# mass_slit7.net
KiCad netlist of a schematic drawn in EAGLE
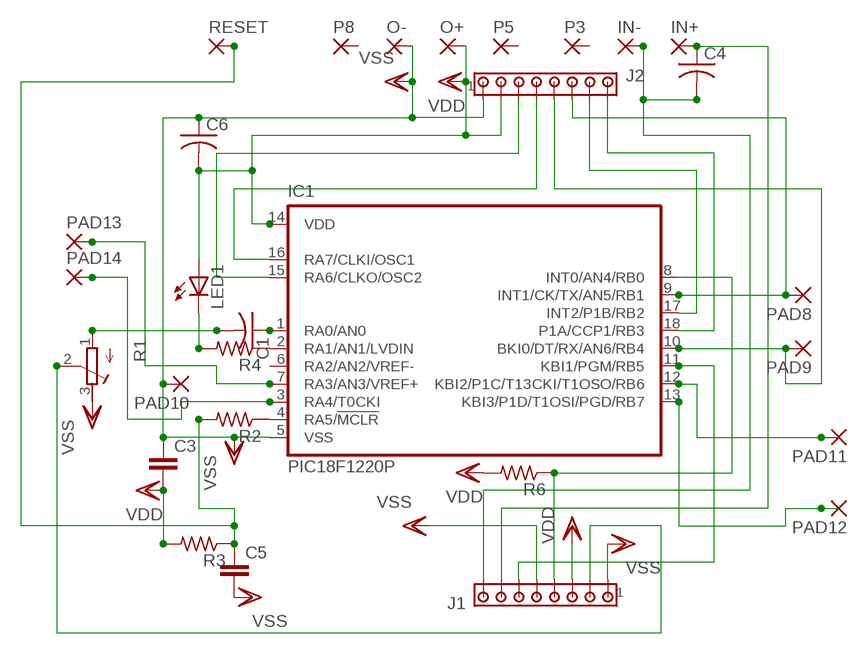
[diagram p0: schematic, sheet 1]

(export (version "E")
  (design (tool "Eeschema 10.0.6"))
  (components
    (comp (ref "C1")
      (value "C-US025-040X050")
      (footprint "eagle-import:C025-040X050")
      (libsource (lib "eagle-import") (part "C-US025-040X050"))
    )
    (comp (ref "C3")
      (value "C5/2.5")
      (footprint "eagle-import:C5B2.5")
      (libsource (lib "eagle-import") (part "C5/2.5"))
    )
    (comp (ref "C4")
      (value "C-US025-040X050")
      (footprint "eagle-import:C025-040X050")
      (libsource (lib "eagle-import") (part "C-US025-040X050"))
    )
    (comp (ref "C5")
      (value "C5/2.5")
      (footprint "eagle-import:C5B2.5")
      (libsource (lib "eagle-import") (part "C5/2.5"))
    )
    (comp (ref "C6")
      (value "C-US025-040X050")
      (footprint "eagle-import:C025-040X050")
      (libsource (lib "eagle-import") (part "C-US025-040X050"))
    )
    (comp (ref "IC1")
      (value "PIC18F1220P")
      (footprint "eagle-import:DIL18")
      (fields (field (name "MF") "MICROCHIP") (field (name "MPN") "PIC18F1220-I/P"))
      (libsource (lib "eagle-import") (part "PIC18F120P2"))
    )
    (comp (ref "IN+")
      (value "1,6/0,9")
      (footprint "eagle-import:1,6_0,9")
      (libsource (lib "eagle-import") (part "1,6/0,9"))
    )
    (comp (ref "IN-")
      (value "1,6/0,9")
      (footprint "eagle-import:1,6_0,9")
      (libsource (lib "eagle-import") (part "1,6/0,9"))
    )
    (comp (ref "J1")
      (value "MTA08-100")
      (footprint "eagle-import:10X08MTA")
      (libsource (lib "eagle-import") (part "MTA08-100"))
    )
    (comp (ref "J2")
      (value "MTA08-100")
      (footprint "eagle-import:10X08MTA")
      (libsource (lib "eagle-import") (part "MTA08-100"))
    )
    (comp (ref "LED1")
      (value "LED3MM")
      (footprint "eagle-import:LED3MM")
      (libsource (lib "eagle-import") (part "LED3MM"))
    )
    (comp (ref "O+")
      (value "1,6/0,9")
      (footprint "eagle-import:1,6_0,9")
      (libsource (lib "eagle-import") (part "1,6/0,9"))
    )
    (comp (ref "O-")
      (value "1,6/0,9")
      (footprint "eagle-import:1,6_0,9")
      (libsource (lib "eagle-import") (part "1,6/0,9"))
    )
    (comp (ref "P3")
      (value "1,6/0,9")
      (footprint "eagle-import:1,6_0,9")
      (libsource (lib "eagle-import") (part "1,6/0,9"))
    )
    (comp (ref "P5")
      (value "1,6/0,9")
      (footprint "eagle-import:1,6_0,9")
      (libsource (lib "eagle-import") (part "1,6/0,9"))
    )
    (comp (ref "P8")
      (value "1,6/0,9")
      (footprint "eagle-import:1,6_0,9")
      (libsource (lib "eagle-import") (part "1,6/0,9"))
    )
    (comp (ref "PAD8")
      (value "1,6/0,9")
      (footprint "eagle-import:1,6_0,9")
      (libsource (lib "eagle-import") (part "1,6/0,9"))
    )
    (comp (ref "PAD9")
      (value "1,6/0,9")
      (footprint "eagle-import:1,6_0,9")
      (libsource (lib "eagle-import") (part "1,6/0,9"))
    )
    (comp (ref "PAD10")
      (value "1,6/0,9")
      (footprint "eagle-import:1,6_0,9")
      (libsource (lib "eagle-import") (part "1,6/0,9"))
    )
    (comp (ref "PAD11")
      (value "1,6/0,9")
      (footprint "eagle-import:1,6_0,9")
      (libsource (lib "eagle-import") (part "1,6/0,9"))
    )
    (comp (ref "PAD12")
      (value "1,6/0,9")
      (footprint "eagle-import:1,6_0,9")
      (libsource (lib "eagle-import") (part "1,6/0,9"))
    )
    (comp (ref "PAD13")
      (value "1,6/0,9")
      (footprint "eagle-import:1,6_0,9")
      (libsource (lib "eagle-import") (part "1,6/0,9"))
    )
    (comp (ref "PAD14")
      (value "1,6/0,9")
      (footprint "eagle-import:1,6_0,9")
      (libsource (lib "eagle-import") (part "1,6/0,9"))
    )
    (comp (ref "R1")
      (value "R-TRIMM3339P")
      (footprint "eagle-import:RTRIM3339P")
      (libsource (lib "eagle-import") (part "R-TRIMM3339P"))
    )
    (comp (ref "R2")
      (value "R-US_0204/2V")
      (footprint "eagle-import:0204V")
      (libsource (lib "eagle-import") (part "R-US_0204/2V"))
    )
    (comp (ref "R3")
      (value "R-US_0204/2V")
      (footprint "eagle-import:0204V")
      (libsource (lib "eagle-import") (part "R-US_0204/2V"))
    )
    (comp (ref "R4")
      (value "R-US_0204/2V")
      (footprint "eagle-import:0204V")
      (libsource (lib "eagle-import") (part "R-US_0204/2V"))
    )
    (comp (ref "R6")
      (value "R-US_0204/2V")
      (footprint "eagle-import:0204V")
      (libsource (lib "eagle-import") (part "R-US_0204/2V"))
    )
    (comp (ref "RESET")
      (value "1,6/0,9")
      (footprint "eagle-import:1,6_0,9")
      (libsource (lib "eagle-import") (part "1,6/0,9"))
    )
  )
  (nets
    (net (code "1") (name "Net-(IC1-BKI0{slash}DT{slash}RX{slash}AN6{slash}RB4)") (class "Default")
      (node (ref "IC1") (pin "10") (pinfunction "BKI0/DT/RX/AN6/RB4_10") (pintype "bidirectional"))
      (node (ref "J2") (pin "5") (pinfunction "5_5") (pintype "passive"))
      (node (ref "PAD9") (pin "1") (pinfunction "P_1") (pintype "passive"))
    )
    (net (code "2") (name "Net-(IC1-INT0{slash}AN4{slash}RB0)") (class "Default")
      (node (ref "IC1") (pin "8") (pinfunction "INT0/AN4/RB0_8") (pintype "bidirectional"))
      (node (ref "J1") (pin "4") (pinfunction "4_4") (pintype "passive"))
      (node (ref "R6") (pin "1") (pinfunction "1_1") (pintype "passive"))
    )
    (net (code "3") (name "Net-(IC1-INT1{slash}CK{slash}TX{slash}AN5{slash}RB1)") (class "Default")
      (node (ref "IC1") (pin "9") (pinfunction "INT1/CK/TX/AN5/RB1_9") (pintype "bidirectional"))
      (node (ref "J2") (pin "6") (pinfunction "6_6") (pintype "passive"))
      (node (ref "PAD8") (pin "1") (pinfunction "P_1") (pintype "passive"))
    )
    (net (code "4") (name "Net-(IC1-INT2{slash}P1B{slash}RB2)") (class "Default")
      (node (ref "IC1") (pin "17") (pinfunction "INT2/P1B/RB2_17") (pintype "bidirectional"))
      (node (ref "J2") (pin "7") (pinfunction "7_7") (pintype "passive"))
    )
    (net (code "5") (name "Net-(IC1-KBI1{slash}PGM{slash}RB5)") (class "Default")
      (node (ref "IC1") (pin "11") (pinfunction "KBI1/PGM/RB5_11") (pintype "bidirectional"))
      (node (ref "J1") (pin "6") (pinfunction "6_6") (pintype "passive"))
    )
    (net (code "6") (name "Net-(IC1-KBI2{slash}P1C{slash}T13CKI{slash}T1OSO{slash}RB6)") (class "Default")
      (node (ref "IC1") (pin "12") (pinfunction "KBI2/P1C/T13CKI/T1OSO/RB6_12") (pintype "bidirectional"))
      (node (ref "PAD11") (pin "1") (pinfunction "P_1") (pintype "passive"))
    )
    (net (code "7") (name "Net-(IC1-KBI3{slash}P1D{slash}T1OSI{slash}PGD{slash}RB7)") (class "Default")
      (node (ref "IC1") (pin "13") (pinfunction "KBI3/P1D/T1OSI/PGD/RB7_13") (pintype "bidirectional"))
      (node (ref "PAD12") (pin "1") (pinfunction "P_1") (pintype "passive"))
    )
    (net (code "8") (name "Net-(IC1-P1A{slash}CCP1{slash}RB3)") (class "Default")
      (node (ref "IC1") (pin "18") (pinfunction "P1A/CCP1/RB3_18") (pintype "bidirectional"))
      (node (ref "J2") (pin "8") (pinfunction "8_8") (pintype "passive"))
    )
    (net (code "9") (name "Net-(IC1-RA0{slash}AN0)") (class "Default")
      (node (ref "C1") (pin "1") (pinfunction "1_1") (pintype "passive"))
      (node (ref "IC1") (pin "1") (pinfunction "RA0/AN0_1") (pintype "bidirectional"))
    )
    (net (code "10") (name "Net-(IC1-RA1{slash}AN1{slash}LVDIN)") (class "Default")
      (node (ref "IC1") (pin "2") (pinfunction "RA1/AN1/LVDIN_2") (pintype "bidirectional"))
      (node (ref "R4") (pin "1") (pinfunction "1_1") (pintype "passive"))
    )
    (net (code "11") (name "Net-(IC1-RA3{slash}AN3{slash}VREF+)") (class "Default")
      (node (ref "IC1") (pin "7") (pinfunction "RA3/AN3/VREF+_7") (pintype "bidirectional"))
      (node (ref "PAD13") (pin "1") (pinfunction "P_1") (pintype "passive"))
    )
    (net (code "12") (name "Net-(IC1-RA4{slash}T0CKI)") (class "Default")
      (node (ref "IC1") (pin "3") (pinfunction "RA4/T0CKI_3") (pintype "bidirectional"))
      (node (ref "PAD14") (pin "1") (pinfunction "P_1") (pintype "passive"))
    )
    (net (code "13") (name "Net-(IC1-RA5{slash}~{MCLR})") (class "Default")
      (node (ref "IC1") (pin "4") (pinfunction "RA5/~{MCLR}_4") (pintype "input"))
      (node (ref "R2") (pin "1") (pinfunction "1_1") (pintype "passive"))
    )
    (net (code "14") (name "Net-(IC1-RA6{slash}CLKO{slash}OSC2)") (class "Default")
      (node (ref "IC1") (pin "15") (pinfunction "RA6/CLKO/OSC2_15") (pintype "bidirectional"))
      (node (ref "J2") (pin "3") (pinfunction "3_3") (pintype "passive"))
    )
    (net (code "15") (name "Net-(IC1-RA7{slash}CLKI{slash}OSC1)") (class "Default")
      (node (ref "IC1") (pin "16") (pinfunction "RA7/CLKI/OSC1_16") (pintype "bidirectional"))
      (node (ref "J2") (pin "4") (pinfunction "4_4") (pintype "passive"))
    )
    (net (code "16") (name "Net-(IN+-P)") (class "Default")
      (node (ref "C4") (pin "1") (pinfunction "1_1") (pintype "passive"))
      (node (ref "IN+") (pin "1") (pinfunction "P_1") (pintype "passive"))
      (node (ref "J1") (pin "7") (pinfunction "7_7") (pintype "passive"))
    )
    (net (code "17") (name "Net-(IN--P)") (class "Default")
      (node (ref "C4") (pin "2") (pinfunction "2_2") (pintype "passive"))
      (node (ref "IN-") (pin "1") (pinfunction "P_1") (pintype "passive"))
      (node (ref "J1") (pin "8") (pinfunction "8_8") (pintype "passive"))
    )
    (net (code "18") (name "Net-(LED1-C)") (class "Default")
      (node (ref "LED1") (pin "K") (pinfunction "C_K") (pintype "passive"))
      (node (ref "R4") (pin "2") (pinfunction "2_2") (pintype "passive"))
    )
    (net (code "19") (name "Net-(R1-A)") (class "Default")
      (node (ref "C1") (pin "2") (pinfunction "2_2") (pintype "passive"))
      (node (ref "R1") (pin "1") (pinfunction "A_1") (pintype "passive"))
    )
    (net (code "20") (name "Net-(R1-S)") (class "Default")
      (node (ref "J1") (pin "2") (pinfunction "2_2") (pintype "passive"))
      (node (ref "R1") (pin "2") (pinfunction "S_2") (pintype "passive"))
    )
    (net (code "21") (name "Net-(RESET-P)") (class "Default")
      (node (ref "C5") (pin "1") (pinfunction "1_1") (pintype "passive"))
      (node (ref "R2") (pin "2") (pinfunction "2_2") (pintype "passive"))
      (node (ref "R3") (pin "1") (pinfunction "1_1") (pintype "passive"))
      (node (ref "RESET") (pin "1") (pinfunction "P_1") (pintype "passive"))
    )
    (net (code "22") (name "VDD") (class "Default")
      (node (ref "C3") (pin "2") (pinfunction "2_2") (pintype "passive"))
      (node (ref "C6") (pin "2") (pinfunction "2_2") (pintype "passive"))
      (node (ref "IC1") (pin "14") (pinfunction "VDD_14") (pintype "power_in"))
      (node (ref "J1") (pin "3") (pinfunction "3_3") (pintype "passive"))
      (node (ref "J2") (pin "2") (pinfunction "2_2") (pintype "passive"))
      (node (ref "LED1") (pin "A") (pinfunction "A_A") (pintype "passive"))
      (node (ref "O+") (pin "1") (pinfunction "P_1") (pintype "passive"))
      (node (ref "R3") (pin "2") (pinfunction "2_2") (pintype "passive"))
      (node (ref "R6") (pin "2") (pinfunction "2_2") (pintype "passive"))
    )
    (net (code "23") (name "VSS") (class "Default")
      (node (ref "C3") (pin "1") (pinfunction "1_1") (pintype "passive"))
      (node (ref "C5") (pin "2") (pinfunction "2_2") (pintype "passive"))
      (node (ref "C6") (pin "1") (pinfunction "1_1") (pintype "passive"))
      (node (ref "IC1") (pin "5") (pinfunction "VSS_5") (pintype "power_in"))
      (node (ref "J1") (pin "1") (pinfunction "1_1") (pintype "passive"))
      (node (ref "J1") (pin "5") (pinfunction "5_5") (pintype "passive"))
      (node (ref "J2") (pin "1") (pinfunction "1_1") (pintype "passive"))
      (node (ref "O-") (pin "1") (pinfunction "P_1") (pintype "passive"))
      (node (ref "PAD10") (pin "1") (pinfunction "P_1") (pintype "passive"))
      (node (ref "R1") (pin "3") (pinfunction "E_3") (pintype "passive"))
    )
    (net (code "24") (name "unconnected-(IC1-RA2{slash}AN2{slash}VREF--Pad6)") (class "Default")
      (node (ref "IC1") (pin "6") (pinfunction "RA2/AN2/VREF-_6") (pintype "bidirectional"))
    )
    (net (code "25") (name "unconnected-(P3-P-Pad1)") (class "Default")
      (node (ref "P3") (pin "1") (pinfunction "P_1") (pintype "passive"))
    )
    (net (code "26") (name "unconnected-(P5-P-Pad1)") (class "Default")
      (node (ref "P5") (pin "1") (pinfunction "P_1") (pintype "passive"))
    )
    (net (code "27") (name "unconnected-(P8-P-Pad1)") (class "Default")
      (node (ref "P8") (pin "1") (pinfunction "P_1") (pintype "passive"))
    )
  )
)
